# EmitterFollower.net
KiCad netlist of a schematic drawn in EAGLE
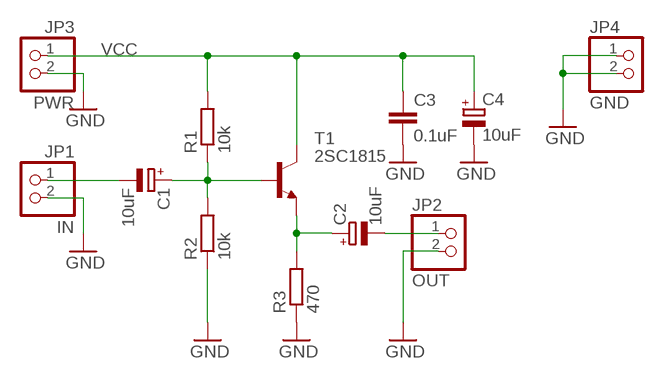
[diagram p0: schematic, sheet 1]

(export (version "E")
  (design (tool "Eeschema 10.0.6"))
  (components
    (comp (ref "C1")
      (value "10uF")
      (footprint "eagle-import:E2,5-6")
      (libsource (lib "eagle-import") (part "CPOL-EUE2.5-6"))
    )
    (comp (ref "C2")
      (value "10uF")
      (footprint "eagle-import:E2,5-6")
      (libsource (lib "eagle-import") (part "CPOL-EUE2.5-6"))
    )
    (comp (ref "C3")
      (value "0.1uF")
      (footprint "eagle-import:C050-024X044")
      (libsource (lib "eagle-import") (part "C-EU050-024X044"))
    )
    (comp (ref "C4")
      (value "10uF")
      (footprint "eagle-import:E2,5-6")
      (libsource (lib "eagle-import") (part "CPOL-EUE2.5-6"))
    )
    (comp (ref "JP1")
      (value "IN")
      (footprint "eagle-import:1X02")
      (libsource (lib "eagle-import") (part "PINHD-1X2"))
    )
    (comp (ref "JP2")
      (value "OUT")
      (footprint "eagle-import:1X02")
      (libsource (lib "eagle-import") (part "PINHD-1X2"))
    )
    (comp (ref "JP3")
      (value "PWR")
      (footprint "eagle-import:1X02")
      (libsource (lib "eagle-import") (part "PINHD-1X2"))
    )
    (comp (ref "JP4")
      (value "GND")
      (footprint "eagle-import:1X02")
      (libsource (lib "eagle-import") (part "PINHD-1X2"))
    )
    (comp (ref "R1")
      (value "10k")
      (footprint "eagle-import:0207_7")
      (libsource (lib "eagle-import") (part "R-EU_0207/7"))
    )
    (comp (ref "R2")
      (value "10k")
      (footprint "eagle-import:0207_7")
      (libsource (lib "eagle-import") (part "R-EU_0207/7"))
    )
    (comp (ref "R3")
      (value "470")
      (footprint "eagle-import:0207_7")
      (libsource (lib "eagle-import") (part "R-EU_0207/7"))
    )
    (comp (ref "T1")
      (value "2SC1815")
      (footprint "eagle-import:TO92-ECB")
      (libsource (lib "eagle-import") (part "-NPN-TO92-ECB"))
    )
  )
  (nets
    (net (code "1") (name "/VCC") (class "Default")
      (node (ref "C3") (pin "1") (pinfunction "1_1") (pintype "passive"))
      (node (ref "C4") (pin "+") (pinfunction "+_+") (pintype "passive"))
      (node (ref "JP3") (pin "1") (pinfunction "1_1") (pintype "passive"))
      (node (ref "R1") (pin "2") (pinfunction "2_2") (pintype "passive"))
      (node (ref "T1") (pin "C") (pinfunction "C_C") (pintype "passive"))
    )
    (net (code "2") (name "GND") (class "Default")
      (node (ref "C3") (pin "2") (pinfunction "2_2") (pintype "passive"))
      (node (ref "C4") (pin "-") (pinfunction "-_-") (pintype "passive"))
      (node (ref "JP1") (pin "2") (pinfunction "2_2") (pintype "passive"))
      (node (ref "JP2") (pin "2") (pinfunction "2_2") (pintype "passive"))
      (node (ref "JP3") (pin "2") (pinfunction "2_2") (pintype "passive"))
      (node (ref "JP4") (pin "1") (pinfunction "1_1") (pintype "passive"))
      (node (ref "JP4") (pin "2") (pinfunction "2_2") (pintype "passive"))
      (node (ref "R2") (pin "1") (pinfunction "1_1") (pintype "passive"))
      (node (ref "R3") (pin "1") (pinfunction "1_1") (pintype "passive"))
    )
    (net (code "3") (name "Net-(C1-Pad+)") (class "Default")
      (node (ref "C1") (pin "+") (pinfunction "+_+") (pintype "passive"))
      (node (ref "R1") (pin "1") (pinfunction "1_1") (pintype "passive"))
      (node (ref "R2") (pin "2") (pinfunction "2_2") (pintype "passive"))
      (node (ref "T1") (pin "B") (pinfunction "B_B") (pintype "passive"))
    )
    (net (code "4") (name "Net-(C1-Pad-)") (class "Default")
      (node (ref "C1") (pin "-") (pinfunction "-_-") (pintype "passive"))
      (node (ref "JP1") (pin "1") (pinfunction "1_1") (pintype "passive"))
    )
    (net (code "5") (name "Net-(C2-Pad+)") (class "Default")
      (node (ref "C2") (pin "+") (pinfunction "+_+") (pintype "passive"))
      (node (ref "R3") (pin "2") (pinfunction "2_2") (pintype "passive"))
      (node (ref "T1") (pin "E") (pinfunction "E_E") (pintype "passive"))
    )
    (net (code "6") (name "Net-(C2-Pad-)") (class "Default")
      (node (ref "C2") (pin "-") (pinfunction "-_-") (pintype "passive"))
      (node (ref "JP2") (pin "1") (pinfunction "1_1") (pintype "passive"))
    )
  )
)
